# DoorBell.net
KiCad netlist of a schematic drawn in EAGLE
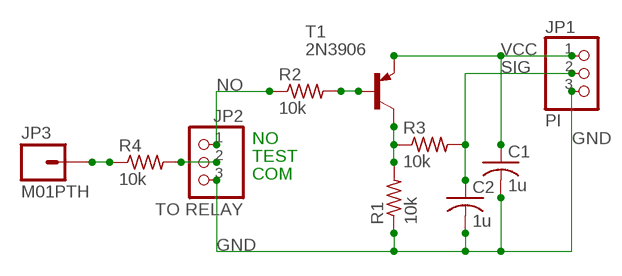
[diagram p0: schematic, sheet 1]

(export (version "E")
  (design (tool "Eeschema 10.0.6"))
  (components
    (comp (ref "C1")
      (value "1u")
      (footprint "eagle-import:C025-025X050")
      (libsource (lib "eagle-import") (part "C-US025-025X050"))
    )
    (comp (ref "C2")
      (value "1u")
      (footprint "eagle-import:C025-025X050")
      (libsource (lib "eagle-import") (part "C-US025-025X050"))
    )
    (comp (ref "JP1")
      (value "PI")
      (footprint "eagle-import:1X03")
      (libsource (lib "eagle-import") (part "PINHD-1X3"))
    )
    (comp (ref "JP2")
      (value "TO RELAY")
      (footprint "eagle-import:1X03")
      (libsource (lib "eagle-import") (part "PINHD-1X3"))
    )
    (comp (ref "JP3")
      (value "M01PTH")
      (footprint "eagle-import:1X01")
      (libsource (lib "eagle-import") (part "M01PTH"))
    )
    (comp (ref "R1")
      (value "10k")
      (footprint "eagle-import:0204_5")
      (libsource (lib "eagle-import") (part "R-US_0204/5"))
    )
    (comp (ref "R2")
      (value "10k")
      (footprint "eagle-import:0204_5")
      (libsource (lib "eagle-import") (part "R-US_0204/5"))
    )
    (comp (ref "R3")
      (value "10k")
      (footprint "eagle-import:0204_5")
      (libsource (lib "eagle-import") (part "R-US_0204/5"))
    )
    (comp (ref "R4")
      (value "10k")
      (footprint "eagle-import:0204_5")
      (libsource (lib "eagle-import") (part "R-US_0204/5"))
    )
    (comp (ref "T1")
      (value "2N3906")
      (footprint "eagle-import:TO92-EBC")
      (libsource (lib "eagle-import") (part "-PNP-TO92-EBC2N3906"))
    )
  )
  (nets
    (net (code "1") (name "/GND") (class "Default")
      (node (ref "C1") (pin "2") (pinfunction "2_2") (pintype "passive"))
      (node (ref "C2") (pin "2") (pinfunction "2_2") (pintype "passive"))
      (node (ref "JP1") (pin "3") (pinfunction "3_3") (pintype "passive"))
      (node (ref "JP2") (pin "3") (pinfunction "3_3") (pintype "passive"))
      (node (ref "R1") (pin "1") (pinfunction "1_1") (pintype "passive"))
    )
    (net (code "2") (name "/NO") (class "Default")
      (node (ref "JP2") (pin "1") (pinfunction "1_1") (pintype "passive"))
      (node (ref "R2") (pin "1") (pinfunction "1_1") (pintype "passive"))
    )
    (net (code "3") (name "/SIG") (class "Default")
      (node (ref "C2") (pin "1") (pinfunction "1_1") (pintype "passive"))
      (node (ref "JP1") (pin "2") (pinfunction "2_2") (pintype "passive"))
      (node (ref "R3") (pin "2") (pinfunction "2_2") (pintype "passive"))
    )
    (net (code "4") (name "/VCC") (class "Default")
      (node (ref "C1") (pin "1") (pinfunction "1_1") (pintype "passive"))
      (node (ref "JP1") (pin "1") (pinfunction "1_1") (pintype "passive"))
      (node (ref "T1") (pin "E") (pinfunction "E_E") (pintype "passive"))
    )
    (net (code "5") (name "Net-(JP2-Pad2)") (class "Default")
      (node (ref "JP2") (pin "2") (pinfunction "2_2") (pintype "passive"))
      (node (ref "R4") (pin "2") (pinfunction "2_2") (pintype "passive"))
    )
    (net (code "6") (name "Net-(JP3-Pad1)") (class "Default")
      (node (ref "JP3") (pin "1") (pinfunction "1_1") (pintype "passive"))
      (node (ref "R4") (pin "1") (pinfunction "1_1") (pintype "passive"))
    )
    (net (code "7") (name "Net-(R1-Pad2)") (class "Default")
      (node (ref "R1") (pin "2") (pinfunction "2_2") (pintype "passive"))
      (node (ref "R3") (pin "1") (pinfunction "1_1") (pintype "passive"))
      (node (ref "T1") (pin "C") (pinfunction "C_C") (pintype "passive"))
    )
    (net (code "8") (name "Net-(R2-Pad2)") (class "Default")
      (node (ref "R2") (pin "2") (pinfunction "2_2") (pintype "passive"))
      (node (ref "T1") (pin "B") (pinfunction "B_B") (pintype "passive"))
    )
  )
)
